# Limit_Switch_Bottom_Vertical_v1_0.net
KiCad netlist of a schematic drawn in Altium Designer
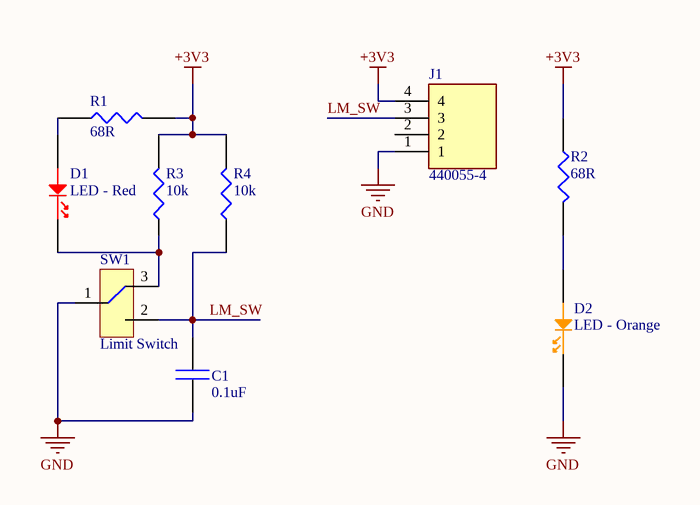
[diagram p0: Limit_Switch_Bottom_Vertical_v1.0.SchDoc]

(export (version "E")
  (design (tool "Eeschema 10.0.6"))
  (components
    (comp (ref "C1")
      (value "0.1uF")
      (footprint "0.1uF 0603")
      (description "CAP CER 0.1UF 16V X7R 0603")
      (fields
        (field (name "MANUFACTURER") "KEMET")
        (field (name "MANUFACTURER PART NUMBER") "C0603C104M4RACTU")
      )
      (libsource (lib "Limit_Switch") (part "C0603C104M4RACTU"))
    )
    (comp (ref "D1")
      (value "LED - Red")
      (footprint "LED RED 0603")
      (description "On a Reel of 5000, 2.4 V Red LED 1608 (0603) SMD, Lite-On LTST-C191KRKT")
      (fields
        (field (name "MANUFACTURER") "Vishay Lite-On")
        (field (name "MANUFACTURER PART NUMBER") "LTST-C191KRKT")
      )
      (libsource (lib "Limit_Switch") (part "LTST-C191KRKT"))
    )
    (comp (ref "D2")
      (value "LED - Orange")
      (footprint "LED0603-Orange")
      (description "LED ORANGE CLEAR SMD")
      (fields
        (field (name "MANUFACTURER") "Vishay Lite-On")
        (field (name "MANUFACTURER PART NUMBER") "LTST-C191KFKT")
      )
      (libsource (lib "Limit_Switch") (part "LTST-C191KFKT"))
    )
    (comp (ref "J1")
      (value "440055-4")
      (footprint "TE_440055-4")
      (description "2.0MM,HDR,4POS,R/A")
      (fields (field (name "MF") "TE Connectivity"))
      (libsource (lib "440055-4 (1)") (part "440055-4"))
    )
    (comp (ref "R1")
      (value "68R")
      (footprint "68R 0603")
      (description "CRGP 0603 68R 1%")
      (fields
        (field (name "MANUFACTURER") "TE Connectivity")
        (field (name "MANUFACTURER PART NUMBER") "CRGP0603F68R")
      )
      (libsource (lib "Limit_Switch") (part "CRGP0603F68R"))
    )
    (comp (ref "R2")
      (value "68R")
      (footprint "68R 0603")
      (description "CRGP 0603 68R 1%")
      (fields
        (field (name "MANUFACTURER") "TE Connectivity")
        (field (name "MANUFACTURER PART NUMBER") "CRGP0603F68R")
      )
      (libsource (lib "Limit_Switch") (part "CRGP0603F68R"))
    )
    (comp (ref "R3")
      (value "10k")
      (footprint "10k R0603")
      (description "RES 10.0K OHM 1/10W 1% 0603")
      (fields
        (field (name "MANUFACTURER") "TE Connectivity")
        (field (name "MANUFACTURER PART NUMBER") "CRG0603F10K/10")
      )
      (libsource (lib "Limit_Switch") (part "CRG0603F10K/10"))
    )
    (comp (ref "R4")
      (value "10k")
      (footprint "10k R0603")
      (description "RES 10.0K OHM 1/10W 1% 0603")
      (fields
        (field (name "MANUFACTURER") "TE Connectivity")
        (field (name "MANUFACTURER PART NUMBER") "CRG0603F10K/10")
      )
      (libsource (lib "Limit_Switch") (part "CRG0603F10K/10"))
    )
    (comp (ref "SW1")
      (value "Limit Switch")
      (footprint "LimitSwitch Horizontal")
      (description "Switch Snap Action N.O./N.C. SPDT Straight Lever 3A 250VAC 0.39N Thru-Hole PC Pins")
      (fields
        (field (name "MANUFACTURER") "E-Switch")
        (field (name "MANUFACTURER PART NUMBER") "SS0750301F040P1A")
      )
      (libsource (lib "Limit_Switch") (part "SS0750301F040P1A"))
    )
  )
  (nets
    (net (code "1") (name "+3V3") (class "Default")
      (node (ref "J1") (pin "4") (pinfunction "4_4") (pintype "passive"))
      (node (ref "R1") (pin "2") (pinfunction "2_2") (pintype "passive"))
      (node (ref "R2") (pin "1") (pinfunction "1_1") (pintype "passive"))
      (node (ref "R3") (pin "2") (pinfunction "2_2") (pintype "passive"))
      (node (ref "R4") (pin "2") (pinfunction "2_2") (pintype "passive"))
    )
    (net (code "2") (name "/LM_SW") (class "Default")
      (node (ref "C1") (pin "2") (pinfunction "2_2") (pintype "passive"))
      (node (ref "J1") (pin "3") (pinfunction "3_3") (pintype "passive"))
      (node (ref "R4") (pin "1") (pinfunction "1_1") (pintype "passive"))
      (node (ref "SW1") (pin "2") (pinfunction "NO_2") (pintype "passive"))
    )
    (net (code "3") (name "GND") (class "Default")
      (node (ref "C1") (pin "1") (pinfunction "1_1") (pintype "passive"))
      (node (ref "D2") (pin "1") (pinfunction "Cathode_1") (pintype "passive"))
      (node (ref "J1") (pin "1") (pinfunction "1_1") (pintype "passive"))
      (node (ref "SW1") (pin "1") (pinfunction "C_1") (pintype "passive"))
    )
    (net (code "4") (name "Net-(D1-Anode)") (class "Default")
      (node (ref "D1") (pin "1") (pinfunction "Anode_1") (pintype "passive"))
      (node (ref "R1") (pin "1") (pinfunction "1_1") (pintype "passive"))
    )
    (net (code "5") (name "Net-(D1-Cathode)") (class "Default")
      (node (ref "D1") (pin "2") (pinfunction "Cathode_2") (pintype "passive"))
      (node (ref "R3") (pin "1") (pinfunction "1_1") (pintype "passive"))
      (node (ref "SW1") (pin "3") (pinfunction "NC_3") (pintype "passive"))
    )
    (net (code "6") (name "Net-(D2-Anode)") (class "Default")
      (node (ref "D2") (pin "2") (pinfunction "Anode_2") (pintype "passive"))
      (node (ref "R2") (pin "2") (pinfunction "2_2") (pintype "passive"))
    )
    (net (code "7") (name "unconnected-(J1-Pad2)") (class "Default")
      (node (ref "J1") (pin "2") (pinfunction "2_2") (pintype "passive"))
    )
  )
)
